# MUX_2x_4x1_74HCT4052D.net
KiCad netlist of a schematic drawn in Altium Designer
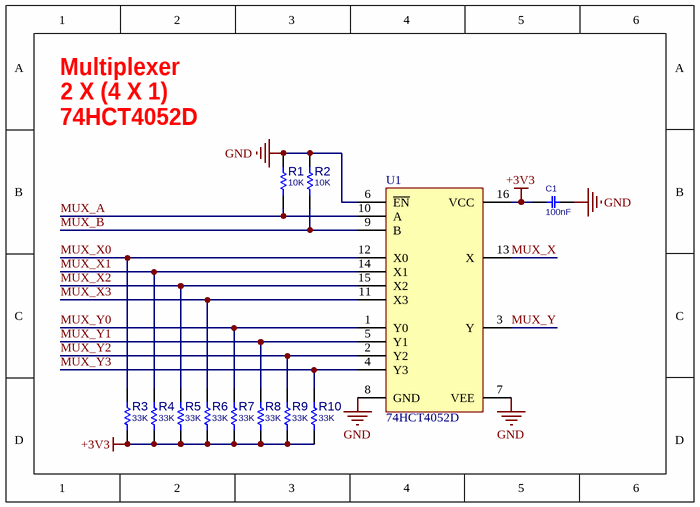
[diagram p0: MUX 2x(4x1) 74HCT4052D.SchDoc]

(export (version "E")
  (design (tool "Eeschema 10.0.6"))
  (components
    (comp (ref "C1")
      (value "100nF")
      (footprint "C0603S")
      (description "CAP, SMD, MLCC")
      (fields (field (name "MANF_P#") "MANF_PART#") (field (name "MANF") "Murata"))
      (libsource (lib "Passive") (part "CAP_SMD_MLCC"))
    )
    (comp (ref "R1")
      (value "10K")
      (footprint "R0603S")
      (description "RES, SMD")
      (fields (field (name "MANF_P#") "RK73H1ETTP4701F") (field (name "MANF") "KOA SPEER"))
      (libsource (lib "Passive") (part "RES_SMD"))
    )
    (comp (ref "R2")
      (value "10K")
      (footprint "R0603S")
      (description "RES, SMD")
      (fields (field (name "MANF_P#") "RK73H1ETTP4701F") (field (name "MANF") "KOA SPEER"))
      (libsource (lib "Passive") (part "RES_SMD"))
    )
    (comp (ref "R3")
      (value "33K")
      (footprint "R0603S")
      (description "RES, SMD")
      (fields (field (name "MANF_P#") "RK73H1ETTP4701F") (field (name "MANF") "KOA SPEER"))
      (libsource (lib "Passive") (part "RES_SMD"))
    )
    (comp (ref "R4")
      (value "33K")
      (footprint "R0603S")
      (description "RES, SMD")
      (fields (field (name "MANF_P#") "RK73H1ETTP4701F") (field (name "MANF") "KOA SPEER"))
      (libsource (lib "Passive") (part "RES_SMD"))
    )
    (comp (ref "R5")
      (value "33K")
      (footprint "R0603S")
      (description "RES, SMD")
      (fields (field (name "MANF_P#") "RK73H1ETTP4701F") (field (name "MANF") "KOA SPEER"))
      (libsource (lib "Passive") (part "RES_SMD"))
    )
    (comp (ref "R6")
      (value "33K")
      (footprint "R0603S")
      (description "RES, SMD")
      (fields (field (name "MANF_P#") "RK73H1ETTP4701F") (field (name "MANF") "KOA SPEER"))
      (libsource (lib "Passive") (part "RES_SMD"))
    )
    (comp (ref "R7")
      (value "33K")
      (footprint "R0603S")
      (description "RES, SMD")
      (fields (field (name "MANF_P#") "RK73H1ETTP4701F") (field (name "MANF") "KOA SPEER"))
      (libsource (lib "Passive") (part "RES_SMD"))
    )
    (comp (ref "R8")
      (value "33K")
      (footprint "R0603S")
      (description "RES, SMD")
      (fields (field (name "MANF_P#") "RK73H1ETTP4701F") (field (name "MANF") "KOA SPEER"))
      (libsource (lib "Passive") (part "RES_SMD"))
    )
    (comp (ref "R9")
      (value "33K")
      (footprint "R0603S")
      (description "RES, SMD")
      (fields (field (name "MANF_P#") "RK73H1ETTP4701F") (field (name "MANF") "KOA SPEER"))
      (libsource (lib "Passive") (part "RES_SMD"))
    )
    (comp (ref "R10")
      (value "33K")
      (footprint "R0603S")
      (description "RES, SMD")
      (fields (field (name "MANF_P#") "RK73H1ETTP4701F") (field (name "MANF") "KOA SPEER"))
      (libsource (lib "Passive") (part "RES_SMD"))
    )
    (comp (ref "U1")
      (value "74HCT4052D")
      (footprint "SO_16")
      (description "Dual 4-Channel Analog Multiplexer/Demultiplexer")
      (fields (field (name "PUBLISHER") "Altium Limited"))
      (libsource (lib "*") (part "MC74HC4052D"))
    )
  )
  (nets
    (net (code "1") (name "+3V3") (class "Default")
      (node (ref "C1") (pin "2") (pinfunction "2_2") (pintype "passive"))
      (node (ref "R10") (pin "1") (pinfunction "1_1") (pintype "passive"))
      (node (ref "R3") (pin "1") (pinfunction "1_1") (pintype "passive"))
      (node (ref "R4") (pin "1") (pinfunction "1_1") (pintype "passive"))
      (node (ref "R5") (pin "1") (pinfunction "1_1") (pintype "passive"))
      (node (ref "R6") (pin "1") (pinfunction "1_1") (pintype "passive"))
      (node (ref "R7") (pin "1") (pinfunction "1_1") (pintype "passive"))
      (node (ref "R8") (pin "1") (pinfunction "1_1") (pintype "passive"))
      (node (ref "R9") (pin "1") (pinfunction "1_1") (pintype "passive"))
      (node (ref "U1") (pin "16") (pinfunction "VCC_16") (pintype "passive"))
    )
    (net (code "2") (name "/MUX_A") (class "Default")
      (node (ref "R1") (pin "1") (pinfunction "1_1") (pintype "passive"))
      (node (ref "U1") (pin "10") (pinfunction "A_10") (pintype "passive"))
    )
    (net (code "3") (name "/MUX_B") (class "Default")
      (node (ref "R2") (pin "1") (pinfunction "1_1") (pintype "passive"))
      (node (ref "U1") (pin "9") (pinfunction "B_9") (pintype "passive"))
    )
    (net (code "4") (name "/MUX_X") (class "Default")
      (node (ref "U1") (pin "13") (pinfunction "X_13") (pintype "passive"))
    )
    (net (code "5") (name "/MUX_X0") (class "Default")
      (node (ref "R3") (pin "2") (pinfunction "2_2") (pintype "passive"))
      (node (ref "U1") (pin "12") (pinfunction "X0_12") (pintype "passive"))
    )
    (net (code "6") (name "/MUX_X1") (class "Default")
      (node (ref "R4") (pin "2") (pinfunction "2_2") (pintype "passive"))
      (node (ref "U1") (pin "14") (pinfunction "X1_14") (pintype "passive"))
    )
    (net (code "7") (name "/MUX_X2") (class "Default")
      (node (ref "R5") (pin "2") (pinfunction "2_2") (pintype "passive"))
      (node (ref "U1") (pin "15") (pinfunction "X2_15") (pintype "passive"))
    )
    (net (code "8") (name "/MUX_X3") (class "Default")
      (node (ref "R6") (pin "2") (pinfunction "2_2") (pintype "passive"))
      (node (ref "U1") (pin "11") (pinfunction "X3_11") (pintype "passive"))
    )
    (net (code "9") (name "/MUX_Y") (class "Default")
      (node (ref "U1") (pin "3") (pinfunction "Y_3") (pintype "passive"))
    )
    (net (code "10") (name "/MUX_Y0") (class "Default")
      (node (ref "R7") (pin "2") (pinfunction "2_2") (pintype "passive"))
      (node (ref "U1") (pin "1") (pinfunction "Y0_1") (pintype "passive"))
    )
    (net (code "11") (name "/MUX_Y1") (class "Default")
      (node (ref "R8") (pin "2") (pinfunction "2_2") (pintype "passive"))
      (node (ref "U1") (pin "5") (pinfunction "Y1_5") (pintype "passive"))
    )
    (net (code "12") (name "/MUX_Y2") (class "Default")
      (node (ref "R9") (pin "2") (pinfunction "2_2") (pintype "passive"))
      (node (ref "U1") (pin "2") (pinfunction "Y2_2") (pintype "passive"))
    )
    (net (code "13") (name "/MUX_Y3") (class "Default")
      (node (ref "R10") (pin "2") (pinfunction "2_2") (pintype "passive"))
      (node (ref "U1") (pin "4") (pinfunction "Y3_4") (pintype "passive"))
    )
    (net (code "14") (name "GND") (class "Default")
      (node (ref "C1") (pin "1") (pinfunction "1_1") (pintype "passive"))
      (node (ref "R1") (pin "2") (pinfunction "2_2") (pintype "passive"))
      (node (ref "R2") (pin "2") (pinfunction "2_2") (pintype "passive"))
      (node (ref "U1") (pin "6") (pinfunction "~{EN}_6") (pintype "passive"))
      (node (ref "U1") (pin "7") (pinfunction "VEE_7") (pintype "passive"))
      (node (ref "U1") (pin "8") (pinfunction "GND_8") (pintype "passive"))
    )
  )
)
